# PicoPrint-Power.net
KiCad netlist of a schematic drawn in Altium Designer
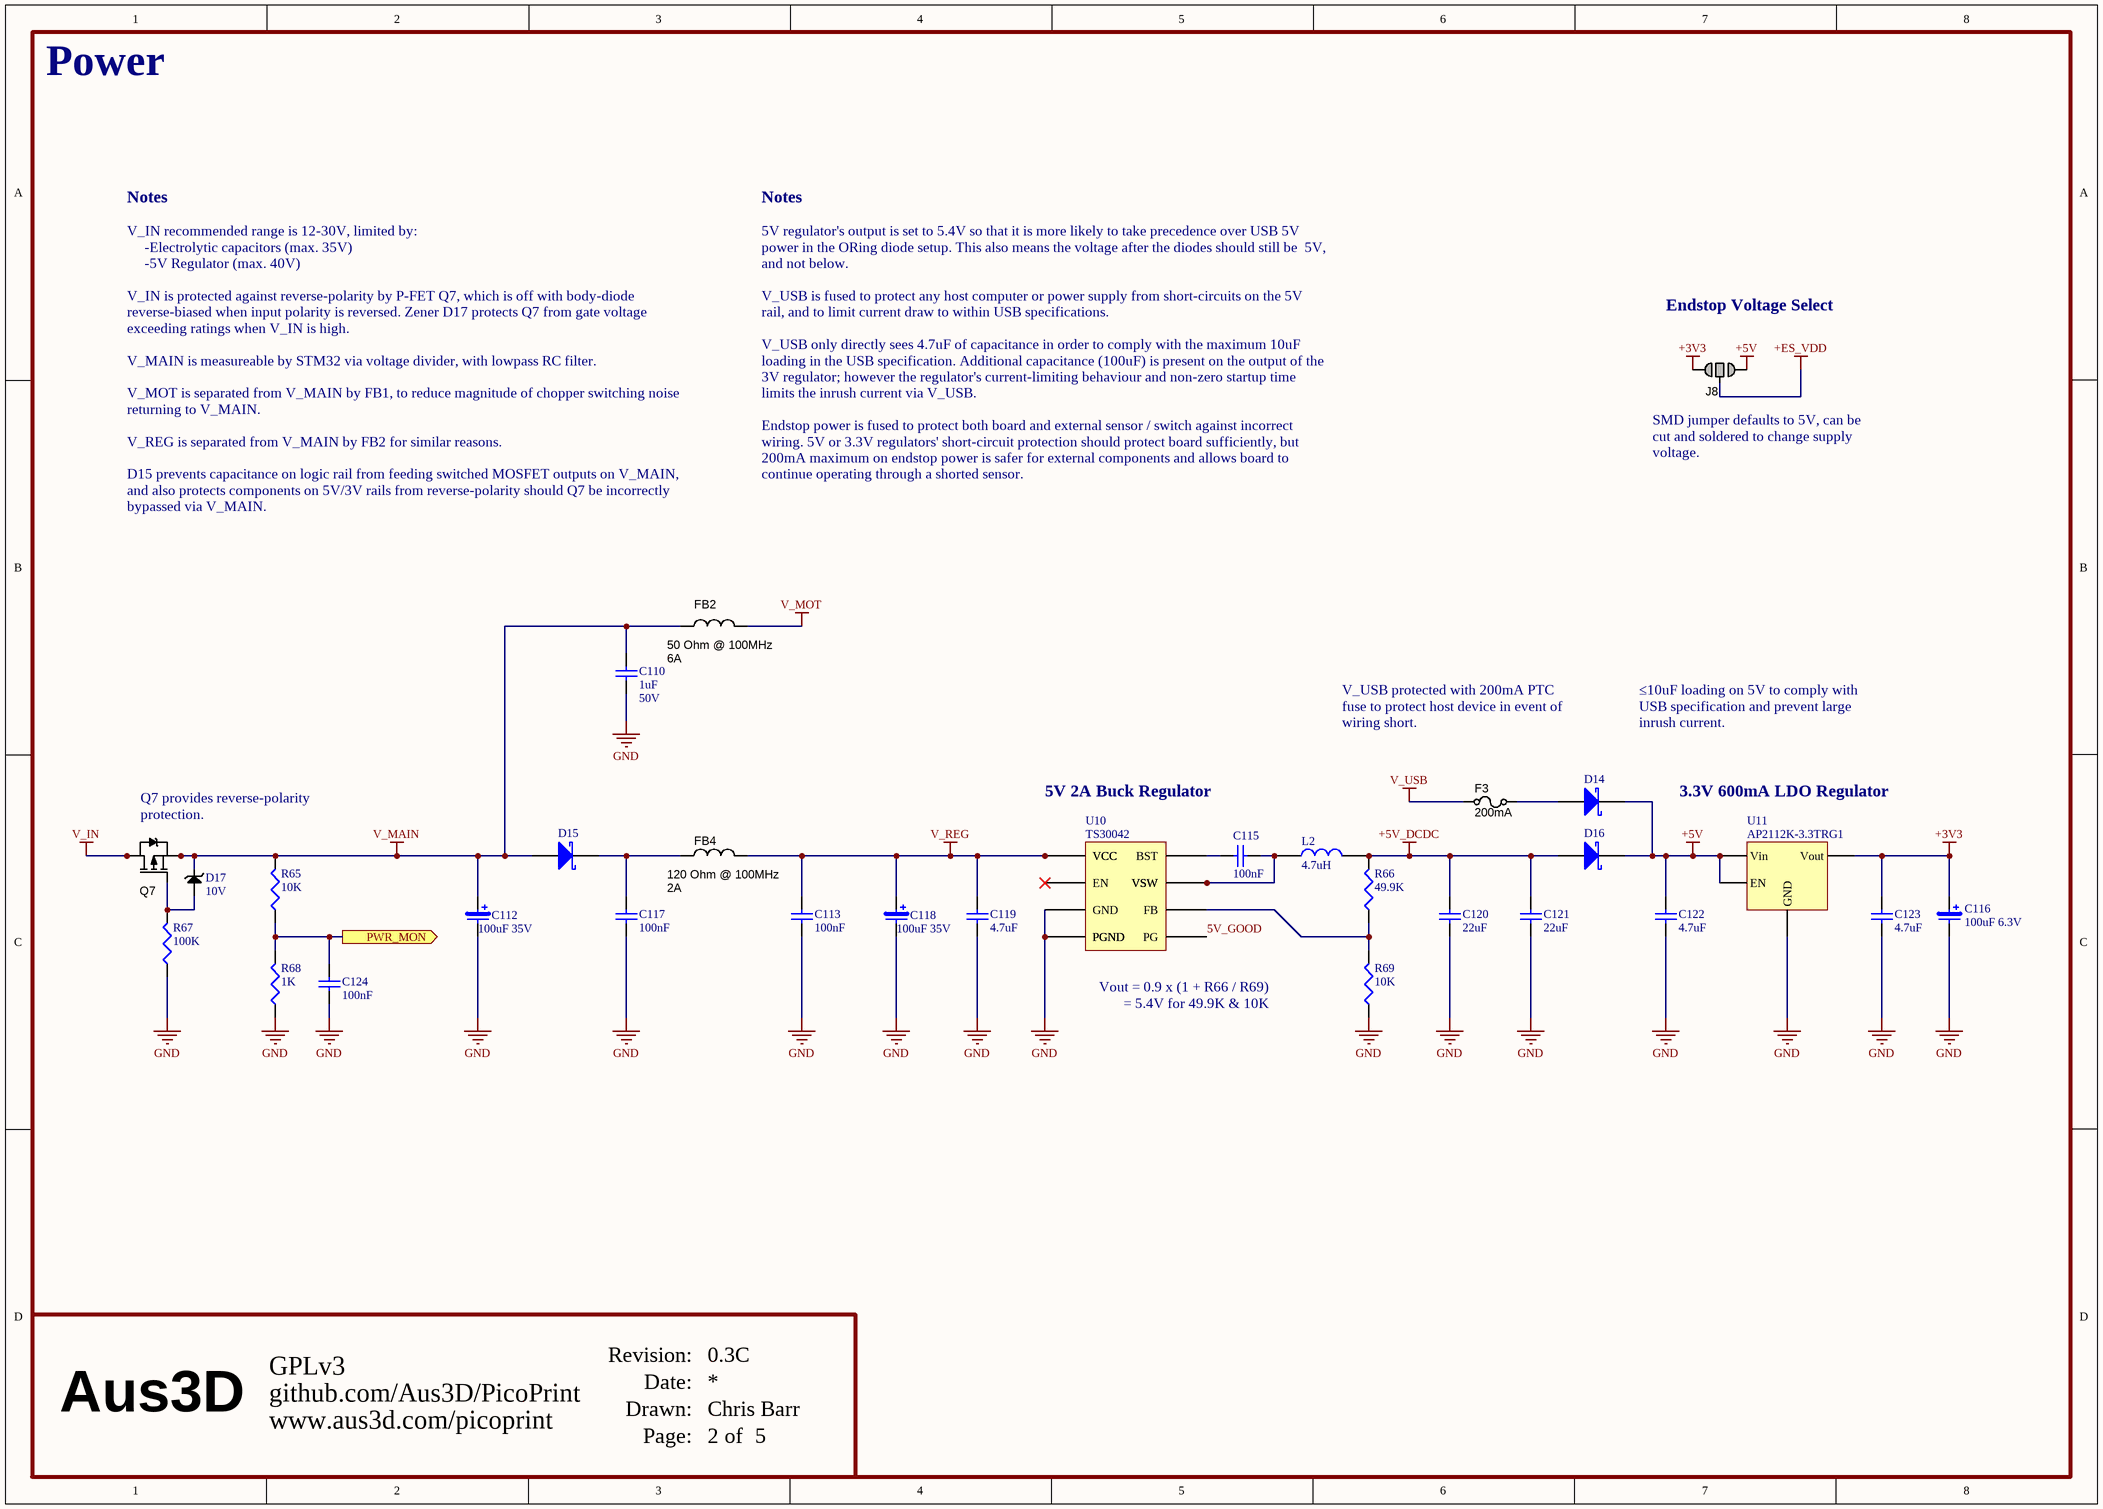
[diagram p0: PicoPrint-Power.SchDoc]

(export (version "E")
  (design (tool "Eeschema 10.0.6"))
  (components
    (comp (ref "C110")
      (value "1uF")
      (footprint "Cap 1608-0603")
      (description "Capacitor (SMD Ceramic)")
      (fields
        (field (name "VOLTAGE") "50V")
        (field (name "Comment") "CapC-0603-1uF 50V")
        (field (name "PUBLISHER") "Altium Limited")
      )
      (libsource (lib "picoprint_library") (part "CapC-0603-1uF 50V"))
    )
    (comp (ref "C112")
      (value "100uF 35V")
      (footprint "CAP EL PANASONIC")
      (description "Capacitor (SMD Polarised Electrolytic)")
      (fields (field (name "Comment") "CapE-6.3-100uF-35V") (field (name "PUBLISHER") "Altium Limited"))
      (libsource (lib "picoprint_library") (part "CapE-6.3-100uF-35V"))
    )
    (comp (ref "C113")
      (value "100nF")
      (footprint "CAP 1005-0402")
      (description "Capacitor (SMD Ceramic)")
      (fields
        (field (name "VOLTAGE") "50V")
        (field (name "Comment") "CapC-0402-100nF-50V")
        (field (name "PUBLISHER") "Altium Limited")
      )
      (libsource (lib "picoprint_library") (part "CapC-0402-100nF-50V"))
    )
    (comp (ref "C115")
      (value "100nF")
      (footprint "CAP 1005-0402")
      (description "Capacitor (SMD Ceramic)")
      (fields (field (name "Comment") "CapC-0402-100nF") (field (name "PUBLISHER") "Altium Limited"))
      (libsource (lib "picoprint_library") (part "CapC-0402-100nF"))
    )
    (comp (ref "C116")
      (value "100uF 6.3V")
      (footprint "CAP EL 5mm")
      (description "Capacitor (SMD Polarised Electrolytic)")
      (fields (field (name "Comment") "CapE-5.0-100uF-6.3V") (field (name "PUBLISHER") "Altium Limited"))
      (libsource (lib "picoprint_library") (part "CapE-5.0-100uF-6.3V"))
    )
    (comp (ref "C117")
      (value "100nF")
      (footprint "CAP 1005-0402")
      (description "Capacitor (SMD Ceramic)")
      (fields
        (field (name "VOLTAGE") "50V")
        (field (name "Comment") "CapC-0402-100nF-50V")
        (field (name "PUBLISHER") "Altium Limited")
      )
      (libsource (lib "picoprint_library") (part "CapC-0402-100nF-50V"))
    )
    (comp (ref "C118")
      (value "100uF 35V")
      (footprint "CAP EL PANASONIC")
      (description "Capacitor (SMD Polarised Electrolytic)")
      (fields (field (name "Comment") "CapE-6.3-100uF-35V") (field (name "PUBLISHER") "Altium Limited"))
      (libsource (lib "picoprint_library") (part "CapE-6.3-100uF-35V"))
    )
    (comp (ref "C119")
      (value "4.7uF")
      (footprint "CAP 3225-1210")
      (description "Capacitor (SMD Ceramic)")
      (fields (field (name "Comment") "CapC-1210-4.7uF-50V") (field (name "PUBLISHER") "Altium Limited"))
      (libsource (lib "picoprint_library") (part "CapC-1210-4.7uF-50V"))
    )
    (comp (ref "C120")
      (value "22uF")
      (footprint "CAPC2012X135N")
      (description "Capacitor (SMD Ceramic)")
      (fields (field (name "Comment") "CapC-0805-22uF 6.3V") (field (name "PUBLISHER") "Altium Limited"))
      (libsource (lib "picoprint_library") (part "CapC-0805-22uF 6.3V"))
    )
    (comp (ref "C121")
      (value "22uF")
      (footprint "CAPC2012X135N")
      (description "Capacitor (SMD Ceramic)")
      (fields (field (name "Comment") "CapC-0805-22uF 6.3V") (field (name "PUBLISHER") "Altium Limited"))
      (libsource (lib "picoprint_library") (part "CapC-0805-22uF 6.3V"))
    )
    (comp (ref "C122")
      (value "4.7uF")
      (footprint "CAP 1005-0402")
      (description "Capacitor (SMD Ceramic)")
      (fields
        (field (name "VOLTAGE") "10V")
        (field (name "Comment") "CapC-0402-4.7uF-10V")
        (field (name "PUBLISHER") "Altium Limited")
      )
      (libsource (lib "picoprint_library") (part "CapC-0402-4.7uF-10V"))
    )
    (comp (ref "C123")
      (value "4.7uF")
      (footprint "CAP 1005-0402")
      (description "Capacitor (SMD Ceramic)")
      (fields
        (field (name "VOLTAGE") "10V")
        (field (name "Comment") "CapC-0402-4.7uF-10V")
        (field (name "PUBLISHER") "Altium Limited")
      )
      (libsource (lib "picoprint_library") (part "CapC-0402-4.7uF-10V"))
    )
    (comp (ref "C124")
      (value "100nF")
      (footprint "CAP 1005-0402")
      (description "Capacitor (SMD Ceramic)")
      (fields (field (name "Comment") "CapC-0402-100nF") (field (name "PUBLISHER") "Altium Limited"))
      (libsource (lib "picoprint_library") (part "CapC-0402-100nF"))
    )
    (comp (ref "D14")
      (value "Schottky 2A 40V SOD-123F")
      (footprint "DIOM2616X08N")
      (description "Diode (SMD)")
      (fields (field (name "PUBLISHER") "Altium Limited"))
      (libsource (lib "picoprint_library") (part "Diode Schottky 2A 40V (SS24FL)"))
    )
    (comp (ref "D15")
      (value "Schottky 2A 40V SOD-123F")
      (footprint "DIOM2616X08N")
      (description "Diode (SMD)")
      (fields (field (name "PUBLISHER") "Altium Limited"))
      (libsource (lib "picoprint_library") (part "Diode Schottky 2A 40V (SS24FL)"))
    )
    (comp (ref "D16")
      (value "Schottky 2A 40V SOD-123F")
      (footprint "DIOM2616X08N")
      (description "Diode (SMD)")
      (fields (field (name "PUBLISHER") "Altium Limited"))
      (libsource (lib "picoprint_library") (part "Diode Schottky 2A 40V (SS24FL)"))
    )
    (comp (ref "D17")
      (value "Zener 10V 150mW SOD523")
      (footprint "SOD523")
      (description "Diode (SMD)")
      (fields (field (name "VOLTAGE") "10V") (field (name "PUBLISHER") "Altium Limited"))
      (libsource (lib "picoprint_library") (part "Diode Zener 10V"))
    )
    (comp (ref "F3")
      (value "200mA")
      (footprint "RES 3216-1206")
      (description "Fuse - 30V 400mA Trip PTC SMD 1206")
      (fields (field (name "Comment") "PTC Resettable Fuse"))
      (libsource (lib "picoprint_library") (part "Fuse - 30V 400mA Trip PTC SMD 1206"))
    )
    (comp (ref "FB2")
      (value "50R @ 100 MHz")
      (footprint "INDC3216X13N")
      (description "Ferrite bead 50 Ohm at 100 MHz 6A 1206 SMD")
      (fields (field (name "IMPEDANCE @ FREQUENCY") "50 Ohm @ 100MHz") (field (name "CURRENT RATING") "6A"))
      (libsource (lib "picoprint_library") (part "FERRITE_50R-100MHz_1206"))
    )
    (comp (ref "FB4")
      (value "120R @ 100 MHz")
      (footprint "INDC1608N")
      (description "Ferrite bead 120 Ohm at 100 MHz 2A 0603 SMD")
      (fields (field (name "IMPEDANCE @ FREQUENCY") "120 Ohm @ 100MHz") (field (name "CURRENT RATING") "2A"))
      (libsource (lib "PBL - Inductors") (part "FERRITE_120R-100MHz_0603"))
    )
    (comp (ref "J8")
      (value "Jumper")
      (footprint "JUMPER-3-NO")
      (description "SMD jumper")
      (libsource (lib "picoprint_library") (part "JUMP3-NO"))
    )
    (comp (ref "L2")
      (value "4.7uH")
      (footprint "INDUCTOR_NRS5030T4R7MMGJ")
      (description "4.7µH Shielded Wirewound Inductor 2.6A 35 mOhm Nonstandard")
      (fields (field (name "Comment") "Inductor SMD 4.7uH 2.6A") (field (name "PUBLISHER") "Altium Limited"))
      (libsource (lib "picoprint_library") (part "Inductor SMD 4.7uH 2.6A"))
    )
    (comp (ref "Q7")
      (value "SI7111EDN-T1-GE3")
      (footprint "PowerPAK 1218-8 Single")
      (description "MOSFET SMD P-CH 30V 60A PowerPAK1212")
      (libsource (lib "picoprint_library") (part "MOSFET - SI7111EDN-T1-GE3"))
    )
    (comp (ref "R65")
      (value "10K")
      (footprint "RESC1005X40N")
      (description "Resistor")
      (fields (field (name "Comment") "Res-0402-10K") (field (name "PUBLISHER") "Altium Limited"))
      (libsource (lib "picoprint_library") (part "Res-0402-10K"))
    )
    (comp (ref "R66")
      (value "49.9K")
      (footprint "RESC1005X40N")
      (description "Resistor")
      (fields (field (name "Comment") "Res-0402-49.9K") (field (name "PUBLISHER") "Altium Limited"))
      (libsource (lib "picoprint_library") (part "Res-0402-49.9K"))
    )
    (comp (ref "R67")
      (value "100K")
      (footprint "RESC1005X40N")
      (description "Resistor")
      (fields (field (name "Comment") "Res-0402-100K") (field (name "PUBLISHER") "Altium Limited"))
      (libsource (lib "picoprint_library") (part "Res-0402-100K"))
    )
    (comp (ref "R68")
      (value "1K")
      (footprint "RESC1005X40N")
      (description "Resistor")
      (fields (field (name "Comment") "Res-0402-1K") (field (name "PUBLISHER") "Altium Limited"))
      (libsource (lib "picoprint_library") (part "Res-0402-1K"))
    )
    (comp (ref "R69")
      (value "10K")
      (footprint "RESC1005X40N")
      (description "Resistor")
      (fields (field (name "Comment") "Res-0402-10K") (field (name "PUBLISHER") "Altium Limited"))
      (libsource (lib "picoprint_library") (part "Res-0402-10K"))
    )
    (comp (ref "U10")
      (value "TS30042")
      (footprint "QFN50P300X300X100_HS-17N")
      (description "Buck Regulator")
      (libsource (lib "picoprint_library") (part "Regulator - TS30042 Buck Regulator"))
    )
    (comp (ref "U11")
      (value "AP2112K-3.3TRG1")
      (footprint "SOT23-5")
      (description "3.3V LDO Regulator")
      (libsource (lib "picoprint_library") (part "Regulator - AP2112K 3.3V Linear Regulator"))
    )
  )
  (nets
    (net (code "1") (name "+3V3") (class "Default")
      (node (ref "C116") (pin "1") (pinfunction "1_1") (pintype "passive"))
      (node (ref "C123") (pin "2") (pinfunction "2_2") (pintype "passive"))
      (node (ref "J8") (pin "1") (pinfunction "1_1") (pintype "passive"))
      (node (ref "U11") (pin "5") (pinfunction "Vout_5") (pintype "passive"))
    )
    (net (code "2") (name "+5V") (class "Default")
      (node (ref "C122") (pin "2") (pinfunction "2_2") (pintype "passive"))
      (node (ref "D14") (pin "K") (pinfunction "K_K") (pintype "passive"))
      (node (ref "D16") (pin "K") (pinfunction "K_K") (pintype "passive"))
      (node (ref "J8") (pin "3") (pinfunction "3_3") (pintype "passive"))
      (node (ref "U11") (pin "1") (pinfunction "Vin_1") (pintype "passive"))
      (node (ref "U11") (pin "3") (pinfunction "EN_3") (pintype "passive"))
    )
    (net (code "3") (name "+5V_DCDC") (class "Default")
      (node (ref "C120") (pin "2") (pinfunction "2_2") (pintype "passive"))
      (node (ref "C121") (pin "2") (pinfunction "2_2") (pintype "passive"))
      (node (ref "D16") (pin "A") (pinfunction "A_A") (pintype "passive"))
      (node (ref "L2") (pin "2") (pinfunction "2_2") (pintype "passive"))
      (node (ref "R66") (pin "2") (pinfunction "2_2") (pintype "passive"))
    )
    (net (code "4") (name "+ES_VDD") (class "Default")
      (node (ref "J8") (pin "2") (pinfunction "2_2") (pintype "passive"))
    )
    (net (code "5") (name "/5V_GOOD") (class "Default")
      (node (ref "U10") (pin "8") (pinfunction "PG_8") (pintype "passive"))
    )
    (net (code "6") (name "/PWR_MON") (class "Default")
      (node (ref "C124") (pin "2") (pinfunction "2_2") (pintype "passive"))
      (node (ref "R65") (pin "1") (pinfunction "1_1") (pintype "passive"))
      (node (ref "R68") (pin "2") (pinfunction "2_2") (pintype "passive"))
    )
    (net (code "7") (name "GND") (class "Default")
      (node (ref "C110") (pin "1") (pinfunction "1_1") (pintype "passive"))
      (node (ref "C112") (pin "2") (pinfunction "2_2") (pintype "passive"))
      (node (ref "C113") (pin "1") (pinfunction "1_1") (pintype "passive"))
      (node (ref "C116") (pin "2") (pinfunction "2_2") (pintype "passive"))
      (node (ref "C117") (pin "1") (pinfunction "1_1") (pintype "passive"))
      (node (ref "C118") (pin "2") (pinfunction "2_2") (pintype "passive"))
      (node (ref "C119") (pin "1") (pinfunction "1_1") (pintype "passive"))
      (node (ref "C120") (pin "1") (pinfunction "1_1") (pintype "passive"))
      (node (ref "C121") (pin "1") (pinfunction "1_1") (pintype "passive"))
      (node (ref "C122") (pin "1") (pinfunction "1_1") (pintype "passive"))
      (node (ref "C123") (pin "1") (pinfunction "1_1") (pintype "passive"))
      (node (ref "C124") (pin "1") (pinfunction "1_1") (pintype "passive"))
      (node (ref "R67") (pin "1") (pinfunction "1_1") (pintype "passive"))
      (node (ref "R68") (pin "1") (pinfunction "1_1") (pintype "passive"))
      (node (ref "R69") (pin "1") (pinfunction "1_1") (pintype "passive"))
      (node (ref "U10") (pin "14") (pinfunction "PGND_14") (pintype "passive"))
      (node (ref "U10") (pin "15") (pinfunction "PGND_15") (pintype "passive"))
      (node (ref "U10") (pin "17") (pinfunction "PGND_17") (pintype "passive"))
      (node (ref "U10") (pin "4") (pinfunction "GND_4") (pintype "passive"))
      (node (ref "U11") (pin "2") (pinfunction "GND_2") (pintype "passive"))
    )
    (net (code "8") (name "Net-(C115-Pad2)") (class "Default")
      (node (ref "C115") (pin "2") (pinfunction "2_2") (pintype "passive"))
      (node (ref "L2") (pin "1") (pinfunction "1_1") (pintype "passive"))
      (node (ref "U10") (pin "1") (pinfunction "VSW_1") (pintype "passive"))
      (node (ref "U10") (pin "12") (pinfunction "VSW_12") (pintype "passive"))
      (node (ref "U10") (pin "13") (pinfunction "VSW_13") (pintype "passive"))
      (node (ref "U10") (pin "16") (pinfunction "VSW_16") (pintype "passive"))
    )
    (net (code "9") (name "Net-(C117-Pad2)") (class "Default")
      (node (ref "C117") (pin "2") (pinfunction "2_2") (pintype "passive"))
      (node (ref "D15") (pin "K") (pinfunction "K_K") (pintype "passive"))
      (node (ref "FB4") (pin "1") (pinfunction "1_1") (pintype "passive"))
    )
    (net (code "10") (name "Net-(D14-PadA)") (class "Default")
      (node (ref "D14") (pin "A") (pinfunction "A_A") (pintype "passive"))
      (node (ref "F3") (pin "2") (pinfunction "2_2") (pintype "passive"))
    )
    (net (code "11") (name "Net-(Q7-G)") (class "Default")
      (node (ref "D17") (pin "A") (pinfunction "A_A") (pintype "passive"))
      (node (ref "Q7") (pin "4") (pinfunction "G_4") (pintype "passive"))
      (node (ref "R67") (pin "2") (pinfunction "2_2") (pintype "passive"))
    )
    (net (code "12") (name "Net-(U10-BST)") (class "Default")
      (node (ref "C115") (pin "1") (pinfunction "1_1") (pintype "passive"))
      (node (ref "U10") (pin "10") (pinfunction "BST_10") (pintype "passive"))
    )
    (net (code "13") (name "Net-(U10-FB)") (class "Default")
      (node (ref "R66") (pin "1") (pinfunction "1_1") (pintype "passive"))
      (node (ref "R69") (pin "2") (pinfunction "2_2") (pintype "passive"))
      (node (ref "U10") (pin "5") (pinfunction "FB_5") (pintype "passive"))
    )
    (net (code "14") (name "V_IN") (class "Default")
      (node (ref "Q7") (pin "5") (pinfunction "D_5") (pintype "passive"))
      (node (ref "Q7") (pin "6") (pinfunction "D_6") (pintype "passive"))
      (node (ref "Q7") (pin "7") (pinfunction "D_7") (pintype "passive"))
      (node (ref "Q7") (pin "8") (pinfunction "D_8") (pintype "passive"))
      (node (ref "Q7") (pin "9") (pinfunction "D_9") (pintype "passive"))
    )
    (net (code "15") (name "V_MAIN") (class "Default")
      (node (ref "C110") (pin "2") (pinfunction "2_2") (pintype "passive"))
      (node (ref "C112") (pin "1") (pinfunction "1_1") (pintype "passive"))
      (node (ref "D15") (pin "A") (pinfunction "A_A") (pintype "passive"))
      (node (ref "D17") (pin "K") (pinfunction "K_K") (pintype "passive"))
      (node (ref "FB2") (pin "1") (pinfunction "1_1") (pintype "passive"))
      (node (ref "Q7") (pin "1") (pinfunction "S_1") (pintype "passive"))
      (node (ref "Q7") (pin "2") (pinfunction "S_2") (pintype "passive"))
      (node (ref "Q7") (pin "3") (pinfunction "S_3") (pintype "passive"))
      (node (ref "R65") (pin "2") (pinfunction "2_2") (pintype "passive"))
    )
    (net (code "16") (name "V_MOT") (class "Default")
      (node (ref "FB2") (pin "2") (pinfunction "2_2") (pintype "passive"))
    )
    (net (code "17") (name "V_REG") (class "Default")
      (node (ref "C113") (pin "2") (pinfunction "2_2") (pintype "passive"))
      (node (ref "C118") (pin "1") (pinfunction "1_1") (pintype "passive"))
      (node (ref "C119") (pin "2") (pinfunction "2_2") (pintype "passive"))
      (node (ref "FB4") (pin "2") (pinfunction "2_2") (pintype "passive"))
      (node (ref "U10") (pin "11") (pinfunction "VCC_11") (pintype "passive"))
      (node (ref "U10") (pin "2") (pinfunction "VCC_2") (pintype "passive"))
      (node (ref "U10") (pin "3") (pinfunction "VCC_3") (pintype "passive"))
    )
    (net (code "18") (name "V_USB") (class "Default")
      (node (ref "F3") (pin "1") (pinfunction "1_1") (pintype "passive"))
    )
    (net (code "19") (name "unconnected-(U10-EN-Pad9)") (class "Default")
      (node (ref "U10") (pin "9") (pinfunction "EN_9") (pintype "passive+no_connect"))
    )
  )
)
